# Sheet1.net
KiCad netlist of a schematic drawn in Altium Designer
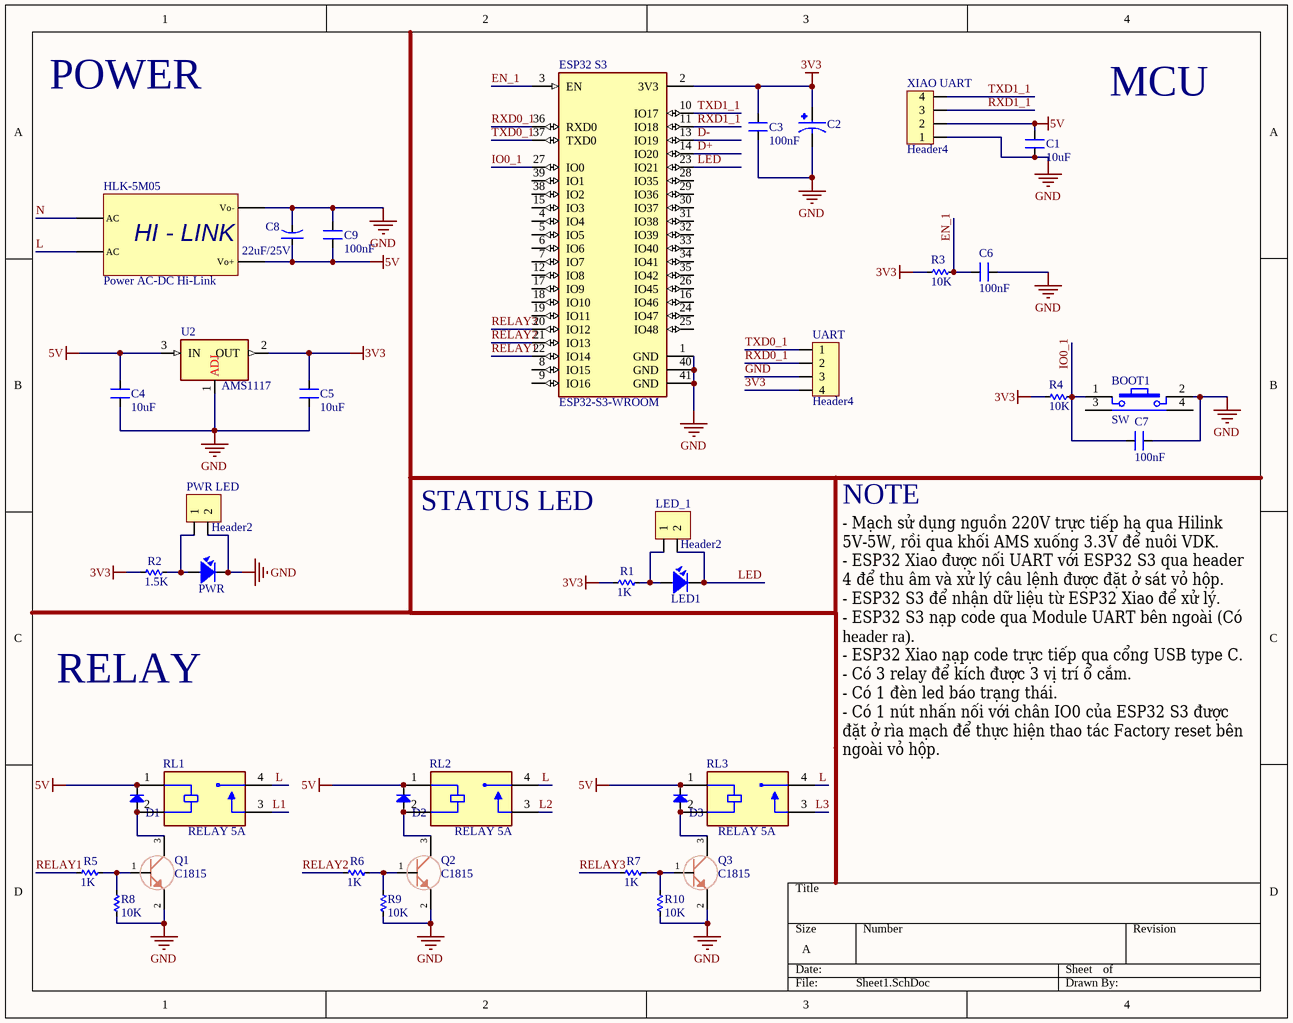
[diagram p0: Sheet1.SchDoc]

(export (version "E")
  (design (tool "Eeschema 10.0.6"))
  (components
    (comp (ref "BOOT1")
      (value "SW")
      (footprint "TACTILE SWITCH TC-0203")
      (description "Switch button 4 pin")
      (libsource (lib "Altium_Devzone") (part "SW4-DIP"))
    )
    (comp (ref "C1")
      (value "10uF")
      (footprint "SM-0805")
      (description "Cap SMD")
      (libsource (lib "My Library") (part "CM"))
    )
    (comp (ref "C2")
      (value "CAP_TANTALUM_SMD")
      (footprint "CAP_TANTALUM_3216")
      (description "Capacitor, Tantalum")
      (fields (field (name "MF") "AVX") (field (name "MP") "TAJB475K025RNJ"))
      (libsource (lib "My Library") (part "CAP_TANTALUM_SMD"))
    )
    (comp (ref "C3")
      (value "100nF")
      (footprint "SM-0805")
      (description "Cap SMD")
      (libsource (lib "My Library") (part "CM"))
    )
    (comp (ref "C4")
      (value "10uF")
      (footprint "SM-0805")
      (description "Cap SMD")
      (libsource (lib "My Library") (part "CM"))
    )
    (comp (ref "C5")
      (value "10uF")
      (footprint "SM-0805")
      (description "Cap SMD")
      (libsource (lib "My Library") (part "CM"))
    )
    (comp (ref "C6")
      (value "100nF")
      (footprint "SM-0805")
      (description "Cap SMD")
      (libsource (lib "My Library") (part "CM"))
    )
    (comp (ref "C7")
      (value "100nF")
      (footprint "SM-0805")
      (description "Cap SMD")
      (libsource (lib "My Library") (part "CM"))
    )
    (comp (ref "C8")
      (value "22uF/25V")
      (footprint "CAP-ALU-SMD-D")
      (description "Polarized Capacitor (Axial)")
      (fields (field (name "PUBLISHER") "Altium Limited"))
      (libsource (lib "My Library") (part "CN-ALU-SMD"))
    )
    (comp (ref "C9")
      (value "100nF")
      (footprint "SM-0805")
      (description "Cap SMD")
      (libsource (lib "My Library") (part "CM"))
    )
    (comp (ref "D1")
      (value "FR207")
      (footprint "DIO-SMD-106")
      (description "Default Diode")
      (fields (field (name "PUBLISHER") "Altium Limited"))
      (libsource (lib "My Library") (part "Diode SMD"))
    )
    (comp (ref "D2")
      (value "FR207")
      (footprint "DIO-SMD-106")
      (description "Default Diode")
      (fields (field (name "PUBLISHER") "Altium Limited"))
      (libsource (lib "My Library") (part "Diode SMD"))
    )
    (comp (ref "D3")
      (value "FR207")
      (footprint "DIO-SMD-106")
      (description "Default Diode")
      (fields (field (name "PUBLISHER") "Altium Limited"))
      (libsource (lib "My Library") (part "Diode SMD"))
    )
    (comp (ref "ESP32 S3")
      (value "ESP32-S3-WROOM")
      (footprint "ESP32-S3-WROOM-1")
      (fields
        (field (name "MF") "{'manufacturer': u'Espressif Systems'}")
        (field (name "MP") "ESP32-S3-WROOM-1-N8")
      )
      (libsource (lib "My Library") (part "ESP32-S3-WROOM"))
    )
    (comp (ref "HLK-5M05")
      (value "Power AC-DC Hi-Link")
      (footprint "HLK-5M05")
      (description "HLK")
      (libsource (lib "My Library") (part "Power AC-DC Hi-Link"))
    )
    (comp (ref "LED1")
      (value "LED")
      (footprint "LED-0805-Red")
      (libsource (lib "My Library") (part "LED SMD"))
    )
    (comp (ref "LED_1")
      (value "Header2")
      (footprint "Header2")
      (description "Header IDC, 2 x 1 Pin Vertical 2.54mm Pitch (Non-Boxed, Male)")
      (fields
        (field (name "MANUFACTURER") "Würth Elektronik eiSos GmbH")
        (field (name "PARTNO") "613002143121")
        (field (name "CREATED BY") "Karrer Zheng")
      )
      (libsource (lib "My Library") (part "Header2"))
    )
    (comp (ref "PWR")
      (value "LED")
      (footprint "LED-0805-Blue")
      (libsource (lib "My Library") (part "LED SMD"))
    )
    (comp (ref "PWR LED")
      (value "Header2")
      (footprint "Header2")
      (description "Header IDC, 2 x 1 Pin Vertical 2.54mm Pitch (Non-Boxed, Male)")
      (fields
        (field (name "MANUFACTURER") "Würth Elektronik eiSos GmbH")
        (field (name "PARTNO") "613002143121")
        (field (name "CREATED BY") "Karrer Zheng")
      )
      (libsource (lib "My Library") (part "Header2"))
    )
    (comp (ref "Q1")
      (value "C1815")
      (footprint "SOT23")
      (libsource (lib "My Library") (part "Transitor SMD"))
    )
    (comp (ref "Q2")
      (value "C1815")
      (footprint "SOT23")
      (libsource (lib "My Library") (part "Transitor SMD"))
    )
    (comp (ref "Q3")
      (value "C1815")
      (footprint "SOT23")
      (libsource (lib "My Library") (part "Transitor SMD"))
    )
    (comp (ref "R1")
      (value "1K")
      (footprint "RES-SMD-0805")
      (description "Resistor")
      (fields
        (field (name "MANUFACTURER") "Generic Components")
        (field (name "PUBLISHER") "Altium Hobart Technology Centre")
      )
      (libsource (lib "My Library") (part "Res-SMD"))
    )
    (comp (ref "R2")
      (value "1.5K")
      (footprint "RES-SMD-0805")
      (description "Resistor")
      (fields
        (field (name "MANUFACTURER") "Generic Components")
        (field (name "PUBLISHER") "Altium Hobart Technology Centre")
      )
      (libsource (lib "My Library") (part "Res-SMD"))
    )
    (comp (ref "R3")
      (value "10K")
      (footprint "RES-SMD-0805")
      (description "Resistor")
      (fields
        (field (name "MANUFACTURER") "Generic Components")
        (field (name "PUBLISHER") "Altium Hobart Technology Centre")
      )
      (libsource (lib "My Library") (part "Res-SMD"))
    )
    (comp (ref "R4")
      (value "10K")
      (footprint "RES-SMD-0805")
      (description "Resistor")
      (fields
        (field (name "MANUFACTURER") "Generic Components")
        (field (name "PUBLISHER") "Altium Hobart Technology Centre")
      )
      (libsource (lib "My Library") (part "Res-SMD"))
    )
    (comp (ref "R5")
      (value "1K")
      (footprint "RES-SMD-0805")
      (description "Resistor")
      (fields
        (field (name "MANUFACTURER") "Generic Components")
        (field (name "PUBLISHER") "Altium Hobart Technology Centre")
      )
      (libsource (lib "My Library") (part "Res-SMD"))
    )
    (comp (ref "R6")
      (value "1K")
      (footprint "RES-SMD-0805")
      (description "Resistor")
      (fields
        (field (name "MANUFACTURER") "Generic Components")
        (field (name "PUBLISHER") "Altium Hobart Technology Centre")
      )
      (libsource (lib "My Library") (part "Res-SMD"))
    )
    (comp (ref "R7")
      (value "1K")
      (footprint "RES-SMD-0805")
      (description "Resistor")
      (fields
        (field (name "MANUFACTURER") "Generic Components")
        (field (name "PUBLISHER") "Altium Hobart Technology Centre")
      )
      (libsource (lib "My Library") (part "Res-SMD"))
    )
    (comp (ref "R8")
      (value "10K")
      (footprint "RES-SMD-0805")
      (description "Resistor")
      (fields
        (field (name "MANUFACTURER") "Generic Components")
        (field (name "PUBLISHER") "Altium Hobart Technology Centre")
      )
      (libsource (lib "My Library") (part "Res-SMD"))
    )
    (comp (ref "R9")
      (value "10K")
      (footprint "RES-SMD-0805")
      (description "Resistor")
      (fields
        (field (name "MANUFACTURER") "Generic Components")
        (field (name "PUBLISHER") "Altium Hobart Technology Centre")
      )
      (libsource (lib "My Library") (part "Res-SMD"))
    )
    (comp (ref "R10")
      (value "10K")
      (footprint "RES-SMD-0805")
      (description "Resistor")
      (fields
        (field (name "MANUFACTURER") "Generic Components")
        (field (name "PUBLISHER") "Altium Hobart Technology Centre")
      )
      (libsource (lib "My Library") (part "Res-SMD"))
    )
    (comp (ref "RL1")
      (value "RELAY 5A")
      (footprint "RELAY 5A")
      (description "18.2 x 10.2 x 15.5 mm, 5 V, 5 A, SPST (1 Form A), Power Relay")
      (fields (field (name "MF") "CUI Devices") (field (name "MP") "PR5-5V-200-1A"))
      (libsource (lib "My Library") (part "RELAY 5A"))
    )
    (comp (ref "RL2")
      (value "RELAY 5A")
      (footprint "RELAY 5A")
      (description "18.2 x 10.2 x 15.5 mm, 5 V, 5 A, SPST (1 Form A), Power Relay")
      (fields (field (name "MF") "CUI Devices") (field (name "MP") "PR5-5V-200-1A"))
      (libsource (lib "My Library") (part "RELAY 5A"))
    )
    (comp (ref "RL3")
      (value "RELAY 5A")
      (footprint "RELAY 5A")
      (description "18.2 x 10.2 x 15.5 mm, 5 V, 5 A, SPST (1 Form A), Power Relay")
      (fields (field (name "MF") "CUI Devices") (field (name "MP") "PR5-5V-200-1A"))
      (libsource (lib "My Library") (part "RELAY 5A"))
    )
    (comp (ref "U2")
      (value "AMS1117")
      (footprint "SOT223-4N")
      (description "IC")
      (libsource (lib "My Library") (part "AMS1117"))
    )
    (comp (ref "UART")
      (value "Header4")
      (footprint "Header4")
      (description "Header IDC, 4 x 1 Pin Vertical 2.54mm Pitch (Non-Boxed, Male)")
      (fields
        (field (name "MANUFACTURER") "Würth Elektronik eiSos GmbH")
        (field (name "PARTNO") "613002143121")
        (field (name "CREATED BY") "Karrer Zheng")
      )
      (libsource (lib "") (part "Header4_1"))
    )
    (comp (ref "XIAO UART")
      (value "Header4")
      (footprint "Header4")
      (description "Header IDC, 4 x 1 Pin Vertical 2.54mm Pitch (Non-Boxed, Male)")
      (fields
        (field (name "MANUFACTURER") "Würth Elektronik eiSos GmbH")
        (field (name "PARTNO") "613002143121")
        (field (name "CREATED BY") "Karrer Zheng")
      )
      (libsource (lib "My Library") (part "Header4"))
    )
  )
  (nets
    (net (code "1") (name "/D+") (class "Default")
      (node (ref "ESP32 S3") (pin "14") (pinfunction "IO20_14") (pintype "bidirectional"))
    )
    (net (code "2") (name "/D-") (class "Default")
      (node (ref "ESP32 S3") (pin "13") (pinfunction "IO19_13") (pintype "bidirectional"))
    )
    (net (code "3") (name "/EN_1") (class "Default")
      (node (ref "C6") (pin "2") (pinfunction "2_2") (pintype "passive"))
      (node (ref "ESP32 S3") (pin "3") (pinfunction "EN_3") (pintype "input"))
      (node (ref "R3") (pin "1") (pinfunction "1_1") (pintype "passive"))
    )
    (net (code "4") (name "/IO0_1") (class "Default")
      (node (ref "BOOT1") (pin "1") (pintype "passive"))
      (node (ref "C7") (pin "2") (pinfunction "2_2") (pintype "passive"))
      (node (ref "ESP32 S3") (pin "27") (pinfunction "IO0_27") (pintype "bidirectional"))
      (node (ref "R4") (pin "1") (pinfunction "1_1") (pintype "passive"))
    )
    (net (code "5") (name "/L") (class "Default")
      (node (ref "HLK-5M05") (pin "2") (pinfunction "AC_2") (pintype "passive"))
      (node (ref "RL1") (pin "4") (pinfunction "COM_4") (pintype "passive"))
      (node (ref "RL2") (pin "4") (pinfunction "COM_4") (pintype "passive"))
      (node (ref "RL3") (pin "4") (pinfunction "COM_4") (pintype "passive"))
    )
    (net (code "6") (name "/L1") (class "Default")
      (node (ref "RL1") (pin "3") (pinfunction "NO_3") (pintype "passive"))
    )
    (net (code "7") (name "/L2") (class "Default")
      (node (ref "RL2") (pin "3") (pinfunction "NO_3") (pintype "passive"))
    )
    (net (code "8") (name "/L3") (class "Default")
      (node (ref "RL3") (pin "3") (pinfunction "NO_3") (pintype "passive"))
    )
    (net (code "9") (name "/LED") (class "Default")
      (node (ref "ESP32 S3") (pin "23") (pinfunction "IO21_23") (pintype "bidirectional"))
      (node (ref "LED1") (pin "2") (pinfunction "2_2") (pintype "passive"))
      (node (ref "LED_1") (pin "2") (pinfunction "2_2") (pintype "passive"))
    )
    (net (code "10") (name "/N") (class "Default")
      (node (ref "HLK-5M05") (pin "1") (pinfunction "AC_1") (pintype "passive"))
    )
    (net (code "11") (name "/RELAY1") (class "Default")
      (node (ref "ESP32 S3") (pin "22") (pinfunction "IO14_22") (pintype "bidirectional"))
      (node (ref "R5") (pin "2") (pinfunction "2_2") (pintype "passive"))
    )
    (net (code "12") (name "/RELAY2") (class "Default")
      (node (ref "ESP32 S3") (pin "21") (pinfunction "IO13_21") (pintype "bidirectional"))
      (node (ref "R6") (pin "2") (pinfunction "2_2") (pintype "passive"))
    )
    (net (code "13") (name "/RELAY3") (class "Default")
      (node (ref "ESP32 S3") (pin "20") (pinfunction "IO12_20") (pintype "bidirectional"))
      (node (ref "R7") (pin "2") (pinfunction "2_2") (pintype "passive"))
    )
    (net (code "14") (name "/RXD0_1") (class "Default")
      (node (ref "ESP32 S3") (pin "36") (pinfunction "RXD0_36") (pintype "bidirectional"))
      (node (ref "UART") (pin "2") (pinfunction "2_2") (pintype "passive"))
    )
    (net (code "15") (name "/RXD1_1") (class "Default")
      (node (ref "ESP32 S3") (pin "11") (pinfunction "IO18_11") (pintype "bidirectional"))
      (node (ref "XIAO UART") (pin "3") (pinfunction "3_3") (pintype "passive"))
    )
    (net (code "16") (name "/TXD0_1") (class "Default")
      (node (ref "ESP32 S3") (pin "37") (pinfunction "TXD0_37") (pintype "bidirectional"))
      (node (ref "UART") (pin "1") (pinfunction "1_1") (pintype "passive"))
    )
    (net (code "17") (name "/TXD1_1") (class "Default")
      (node (ref "ESP32 S3") (pin "10") (pinfunction "IO17_10") (pintype "bidirectional"))
      (node (ref "XIAO UART") (pin "4") (pinfunction "4_4") (pintype "passive"))
    )
    (net (code "18") (name "3V3") (class "Default")
      (node (ref "C2") (pin "1") (pinfunction "1_1") (pintype "passive"))
      (node (ref "C3") (pin "2") (pinfunction "2_2") (pintype "passive"))
      (node (ref "C5") (pin "2") (pinfunction "2_2") (pintype "passive"))
      (node (ref "ESP32 S3") (pin "2") (pinfunction "3V3_2") (pintype "power_in"))
      (node (ref "R1") (pin "2") (pinfunction "2_2") (pintype "passive"))
      (node (ref "R2") (pin "2") (pinfunction "2_2") (pintype "passive"))
      (node (ref "R3") (pin "2") (pinfunction "2_2") (pintype "passive"))
      (node (ref "R4") (pin "2") (pinfunction "2_2") (pintype "passive"))
      (node (ref "U2") (pin "2") (pinfunction "OUT_2") (pintype "output"))
      (node (ref "UART") (pin "4") (pinfunction "4_4") (pintype "passive"))
    )
    (net (code "19") (name "5V") (class "Default")
      (node (ref "C1") (pin "1") (pinfunction "1_1") (pintype "passive"))
      (node (ref "C4") (pin "2") (pinfunction "2_2") (pintype "passive"))
      (node (ref "C8") (pin "1") (pinfunction "1_1") (pintype "passive"))
      (node (ref "C9") (pin "1") (pinfunction "1_1") (pintype "passive"))
      (node (ref "D1") (pin "2") (pinfunction "K_2") (pintype "passive"))
      (node (ref "D2") (pin "2") (pinfunction "K_2") (pintype "passive"))
      (node (ref "D3") (pin "2") (pinfunction "K_2") (pintype "passive"))
      (node (ref "HLK-5M05") (pin "4") (pinfunction "Vo+_4") (pintype "passive"))
      (node (ref "RL1") (pin "1") (pinfunction "COIL1_1") (pintype "passive"))
      (node (ref "RL2") (pin "1") (pinfunction "COIL1_1") (pintype "passive"))
      (node (ref "RL3") (pin "1") (pinfunction "COIL1_1") (pintype "passive"))
      (node (ref "U2") (pin "3") (pinfunction "IN_3") (pintype "input"))
      (node (ref "XIAO UART") (pin "2") (pinfunction "2_2") (pintype "passive"))
    )
    (net (code "20") (name "GND") (class "Default")
      (node (ref "BOOT1") (pin "2") (pintype "passive"))
      (node (ref "C1") (pin "2") (pinfunction "2_2") (pintype "passive"))
      (node (ref "C2") (pin "2") (pinfunction "2_2") (pintype "passive"))
      (node (ref "C3") (pin "1") (pinfunction "1_1") (pintype "passive"))
      (node (ref "C4") (pin "1") (pinfunction "1_1") (pintype "passive"))
      (node (ref "C5") (pin "1") (pinfunction "1_1") (pintype "passive"))
      (node (ref "C6") (pin "1") (pinfunction "1_1") (pintype "passive"))
      (node (ref "C7") (pin "1") (pinfunction "1_1") (pintype "passive"))
      (node (ref "C8") (pin "2") (pinfunction "2_2") (pintype "passive"))
      (node (ref "C9") (pin "2") (pinfunction "2_2") (pintype "passive"))
      (node (ref "ESP32 S3") (pin "1") (pinfunction "GND_1") (pintype "power_in"))
      (node (ref "ESP32 S3") (pin "40") (pinfunction "GND_40") (pintype "power_in"))
      (node (ref "ESP32 S3") (pin "41") (pinfunction "GND_41") (pintype "power_in"))
      (node (ref "HLK-5M05") (pin "3") (pinfunction "Vo-_3") (pintype "passive"))
      (node (ref "PWR") (pin "2") (pinfunction "2_2") (pintype "passive"))
      (node (ref "PWR LED") (pin "2") (pinfunction "2_2") (pintype "passive"))
      (node (ref "Q1") (pin "2") (pinfunction "E_2") (pintype "passive"))
      (node (ref "Q2") (pin "2") (pinfunction "E_2") (pintype "passive"))
      (node (ref "Q3") (pin "2") (pinfunction "E_2") (pintype "passive"))
      (node (ref "R10") (pin "2") (pinfunction "2_2") (pintype "passive"))
      (node (ref "R8") (pin "2") (pinfunction "2_2") (pintype "passive"))
      (node (ref "R9") (pin "2") (pinfunction "2_2") (pintype "passive"))
      (node (ref "U2") (pin "1") (pinfunction "ADJ_1") (pintype "passive"))
      (node (ref "UART") (pin "3") (pinfunction "3_3") (pintype "passive"))
      (node (ref "XIAO UART") (pin "1") (pinfunction "1_1") (pintype "passive"))
    )
    (net (code "21") (name "Net-(D1-A)") (class "Default")
      (node (ref "D1") (pin "1") (pinfunction "A_1") (pintype "passive"))
      (node (ref "Q1") (pin "3") (pinfunction "C_3") (pintype "passive"))
      (node (ref "RL1") (pin "2") (pinfunction "COIL2_2") (pintype "passive"))
    )
    (net (code "22") (name "Net-(D2-A)") (class "Default")
      (node (ref "D2") (pin "1") (pinfunction "A_1") (pintype "passive"))
      (node (ref "Q2") (pin "3") (pinfunction "C_3") (pintype "passive"))
      (node (ref "RL2") (pin "2") (pinfunction "COIL2_2") (pintype "passive"))
    )
    (net (code "23") (name "Net-(D3-A)") (class "Default")
      (node (ref "D3") (pin "1") (pinfunction "A_1") (pintype "passive"))
      (node (ref "Q3") (pin "3") (pinfunction "C_3") (pintype "passive"))
      (node (ref "RL3") (pin "2") (pinfunction "COIL2_2") (pintype "passive"))
    )
    (net (code "24") (name "Net-(LED1-Pad1)") (class "Default")
      (node (ref "LED1") (pin "1") (pinfunction "1_1") (pintype "passive"))
      (node (ref "LED_1") (pin "1") (pinfunction "1_1") (pintype "passive"))
      (node (ref "R1") (pin "1") (pinfunction "1_1") (pintype "passive"))
    )
    (net (code "25") (name "Net-(PWR LED-Pad1)") (class "Default")
      (node (ref "PWR") (pin "1") (pinfunction "1_1") (pintype "passive"))
      (node (ref "PWR LED") (pin "1") (pinfunction "1_1") (pintype "passive"))
      (node (ref "R2") (pin "1") (pinfunction "1_1") (pintype "passive"))
    )
    (net (code "26") (name "Net-(Q1-B)") (class "Default")
      (node (ref "Q1") (pin "1") (pinfunction "B_1") (pintype "passive"))
      (node (ref "R5") (pin "1") (pinfunction "1_1") (pintype "passive"))
      (node (ref "R8") (pin "1") (pinfunction "1_1") (pintype "passive"))
    )
    (net (code "27") (name "Net-(Q2-B)") (class "Default")
      (node (ref "Q2") (pin "1") (pinfunction "B_1") (pintype "passive"))
      (node (ref "R6") (pin "1") (pinfunction "1_1") (pintype "passive"))
      (node (ref "R9") (pin "1") (pinfunction "1_1") (pintype "passive"))
    )
    (net (code "28") (name "Net-(Q3-B)") (class "Default")
      (node (ref "Q3") (pin "1") (pinfunction "B_1") (pintype "passive"))
      (node (ref "R10") (pin "1") (pinfunction "1_1") (pintype "passive"))
      (node (ref "R7") (pin "1") (pinfunction "1_1") (pintype "passive"))
    )
    (net (code "29") (name "unconnected-(BOOT1-Pad3)") (class "Default")
      (node (ref "BOOT1") (pin "3") (pintype "passive"))
    )
    (net (code "30") (name "unconnected-(BOOT1-Pad4)") (class "Default")
      (node (ref "BOOT1") (pin "4") (pintype "passive"))
    )
    (net (code "31") (name "unconnected-(ESP32 S3-IO1-Pad39)") (class "Default")
      (node (ref "ESP32 S3") (pin "39") (pinfunction "IO1_39") (pintype "bidirectional"))
    )
    (net (code "32") (name "unconnected-(ESP32 S3-IO2-Pad38)") (class "Default")
      (node (ref "ESP32 S3") (pin "38") (pinfunction "IO2_38") (pintype "bidirectional"))
    )
    (net (code "33") (name "unconnected-(ESP32 S3-IO3-Pad15)") (class "Default")
      (node (ref "ESP32 S3") (pin "15") (pinfunction "IO3_15") (pintype "bidirectional"))
    )
    (net (code "34") (name "unconnected-(ESP32 S3-IO4-Pad4)") (class "Default")
      (node (ref "ESP32 S3") (pin "4") (pinfunction "IO4_4") (pintype "bidirectional"))
    )
    (net (code "35") (name "unconnected-(ESP32 S3-IO5-Pad5)") (class "Default")
      (node (ref "ESP32 S3") (pin "5") (pinfunction "IO5_5") (pintype "bidirectional"))
    )
    (net (code "36") (name "unconnected-(ESP32 S3-IO6-Pad6)") (class "Default")
      (node (ref "ESP32 S3") (pin "6") (pinfunction "IO6_6") (pintype "bidirectional"))
    )
    (net (code "37") (name "unconnected-(ESP32 S3-IO7-Pad7)") (class "Default")
      (node (ref "ESP32 S3") (pin "7") (pinfunction "IO7_7") (pintype "bidirectional"))
    )
    (net (code "38") (name "unconnected-(ESP32 S3-IO8-Pad12)") (class "Default")
      (node (ref "ESP32 S3") (pin "12") (pinfunction "IO8_12") (pintype "bidirectional"))
    )
    (net (code "39") (name "unconnected-(ESP32 S3-IO9-Pad17)") (class "Default")
      (node (ref "ESP32 S3") (pin "17") (pinfunction "IO9_17") (pintype "bidirectional"))
    )
    (net (code "40") (name "unconnected-(ESP32 S3-IO10-Pad18)") (class "Default")
      (node (ref "ESP32 S3") (pin "18") (pinfunction "IO10_18") (pintype "bidirectional"))
    )
    (net (code "41") (name "unconnected-(ESP32 S3-IO11-Pad19)") (class "Default")
      (node (ref "ESP32 S3") (pin "19") (pinfunction "IO11_19") (pintype "bidirectional"))
    )
    (net (code "42") (name "unconnected-(ESP32 S3-IO15-Pad8)") (class "Default")
      (node (ref "ESP32 S3") (pin "8") (pinfunction "IO15_8") (pintype "bidirectional"))
    )
    (net (code "43") (name "unconnected-(ESP32 S3-IO16-Pad9)") (class "Default")
      (node (ref "ESP32 S3") (pin "9") (pinfunction "IO16_9") (pintype "bidirectional"))
    )
    (net (code "44") (name "unconnected-(ESP32 S3-IO35-Pad28)") (class "Default")
      (node (ref "ESP32 S3") (pin "28") (pinfunction "IO35_28") (pintype "bidirectional"))
    )
    (net (code "45") (name "unconnected-(ESP32 S3-IO36-Pad29)") (class "Default")
      (node (ref "ESP32 S3") (pin "29") (pinfunction "IO36_29") (pintype "bidirectional"))
    )
    (net (code "46") (name "unconnected-(ESP32 S3-IO37-Pad30)") (class "Default")
      (node (ref "ESP32 S3") (pin "30") (pinfunction "IO37_30") (pintype "bidirectional"))
    )
    (net (code "47") (name "unconnected-(ESP32 S3-IO38-Pad31)") (class "Default")
      (node (ref "ESP32 S3") (pin "31") (pinfunction "IO38_31") (pintype "bidirectional"))
    )
    (net (code "48") (name "unconnected-(ESP32 S3-IO39-Pad32)") (class "Default")
      (node (ref "ESP32 S3") (pin "32") (pinfunction "IO39_32") (pintype "bidirectional"))
    )
    (net (code "49") (name "unconnected-(ESP32 S3-IO40-Pad33)") (class "Default")
      (node (ref "ESP32 S3") (pin "33") (pinfunction "IO40_33") (pintype "bidirectional"))
    )
    (net (code "50") (name "unconnected-(ESP32 S3-IO41-Pad34)") (class "Default")
      (node (ref "ESP32 S3") (pin "34") (pinfunction "IO41_34") (pintype "bidirectional"))
    )
    (net (code "51") (name "unconnected-(ESP32 S3-IO42-Pad35)") (class "Default")
      (node (ref "ESP32 S3") (pin "35") (pinfunction "IO42_35") (pintype "bidirectional"))
    )
    (net (code "52") (name "unconnected-(ESP32 S3-IO45-Pad26)") (class "Default")
      (node (ref "ESP32 S3") (pin "26") (pinfunction "IO45_26") (pintype "bidirectional"))
    )
    (net (code "53") (name "unconnected-(ESP32 S3-IO46-Pad16)") (class "Default")
      (node (ref "ESP32 S3") (pin "16") (pinfunction "IO46_16") (pintype "bidirectional"))
    )
    (net (code "54") (name "unconnected-(ESP32 S3-IO47-Pad24)") (class "Default")
      (node (ref "ESP32 S3") (pin "24") (pinfunction "IO47_24") (pintype "bidirectional"))
    )
    (net (code "55") (name "unconnected-(ESP32 S3-IO48-Pad25)") (class "Default")
      (node (ref "ESP32 S3") (pin "25") (pinfunction "IO48_25") (pintype "bidirectional"))
    )
  )
)
